# p2-001.net
KiCad netlist of a schematic drawn in EAGLE
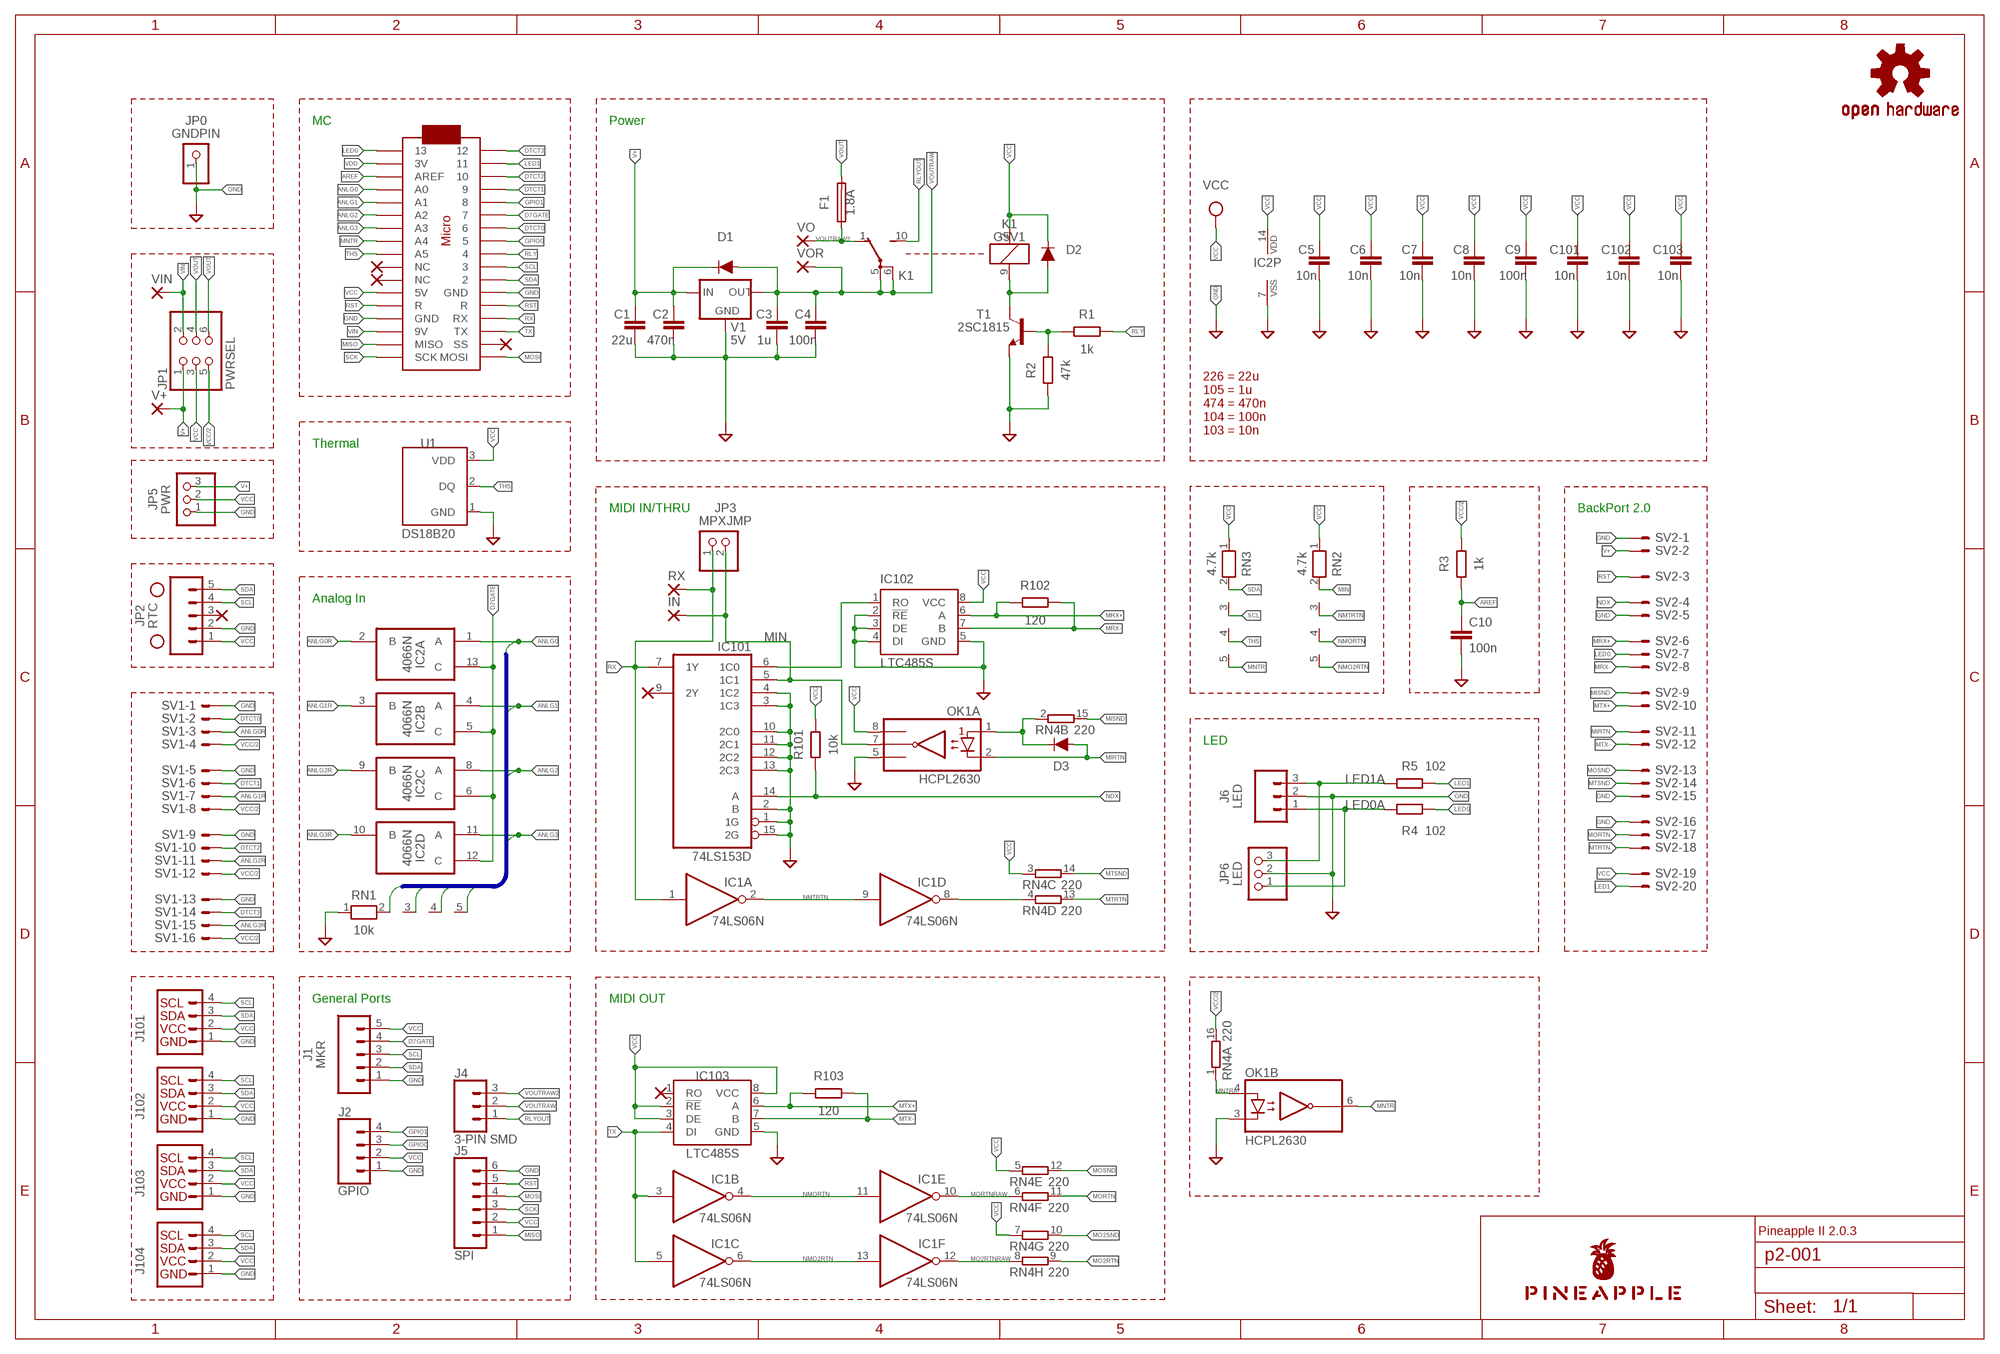
[diagram p0: schematic, sheet 1]

(export (version "E")
  (design (tool "Eeschema 10.0.6"))
  (components
    (comp (ref "C1")
      (value "22u")
      (footprint "eagle-import:C025-050X050")
      (libsource (lib "eagle-import") (part "C-EU025-050X050"))
    )
    (comp (ref "C2")
      (value "470n")
      (footprint "eagle-import:C050-024X044")
      (libsource (lib "eagle-import") (part "C-EU050-024X044"))
    )
    (comp (ref "C3")
      (value "1u")
      (footprint "eagle-import:C050-024X044")
      (libsource (lib "eagle-import") (part "C-EU050-024X044"))
    )
    (comp (ref "C4")
      (value "100n")
      (footprint "eagle-import:C025-024X044")
      (libsource (lib "eagle-import") (part "C-EU025-024X044"))
    )
    (comp (ref "C5")
      (value "10n")
      (footprint "eagle-import:C025-024X044")
      (libsource (lib "eagle-import") (part "resistor_348_C-EU025-024X044"))
    )
    (comp (ref "C6")
      (value "10n")
      (footprint "eagle-import:C025-024X044")
      (libsource (lib "eagle-import") (part "resistor_348_C-EU025-024X044"))
    )
    (comp (ref "C7")
      (value "10n")
      (footprint "eagle-import:C025-024X044")
      (libsource (lib "eagle-import") (part "resistor_348_C-EU025-024X044"))
    )
    (comp (ref "C8")
      (value "10n")
      (footprint "eagle-import:C025-024X044")
      (libsource (lib "eagle-import") (part "resistor_348_C-EU025-024X044"))
    )
    (comp (ref "C9")
      (value "100n")
      (footprint "eagle-import:C025-024X044")
      (libsource (lib "eagle-import") (part "C-EU025-024X044"))
    )
    (comp (ref "C10")
      (value "100n")
      (footprint "eagle-import:C025-024X044")
      (libsource (lib "eagle-import") (part "C-EU025-024X044"))
    )
    (comp (ref "C101")
      (value "10n")
      (footprint "eagle-import:C2012")
      (libsource (lib "eagle-import") (part "C-EUC2012"))
    )
    (comp (ref "C102")
      (value "10n")
      (footprint "eagle-import:C2012")
      (libsource (lib "eagle-import") (part "C-EUC2012"))
    )
    (comp (ref "C103")
      (value "10n")
      (footprint "eagle-import:C2012")
      (libsource (lib "eagle-import") (part "C-EUC2012"))
    )
    (comp (ref "D1")
      (value "DIODE-1N4148")
      (footprint "eagle-import:DIODE-1N4148")
      (libsource (lib "eagle-import") (part "DIODE-1N4148"))
    )
    (comp (ref "D2")
      (value "DIODE-1N4148")
      (footprint "eagle-import:DIODE-1N4148")
      (libsource (lib "eagle-import") (part "DIODE-1N4148"))
    )
    (comp (ref "D3")
      (value "DIODE-1N4148")
      (footprint "eagle-import:DIODE-1N4148")
      (libsource (lib "eagle-import") (part "DIODE-1N4148"))
    )
    (comp (ref "F1")
      (value "1.8A")
      (footprint "eagle-import:TE5")
      (libsource (lib "eagle-import") (part "TE5"))
    )
    (comp (ref "H1")
      (value "STAND-OFF")
      (footprint "eagle-import:STAND-OFF")
      (libsource (lib "eagle-import") (part "STAND-OFF"))
    )
    (comp (ref "H2")
      (value "STAND-OFF")
      (footprint "eagle-import:STAND-OFF")
      (libsource (lib "eagle-import") (part "STAND-OFF"))
    )
    (comp (ref "IC1")
      (value "74LS06N")
      (footprint "eagle-import:DIL14")
      (libsource (lib "eagle-import") (part "7406NLS"))
    )
    (comp (ref "IC2")
      (value "4066N")
      (footprint "eagle-import:DIL14")
      (libsource (lib "eagle-import") (part "4066N"))
    )
    (comp (ref "IC101")
      (value "74LS153D")
      (footprint "eagle-import:SO16")
      (libsource (lib "eagle-import") (part "74153DLS"))
    )
    (comp (ref "IC102")
      (value "LTC485S")
      (footprint "eagle-import:SOIC8")
      (libsource (lib "eagle-import") (part "LTC485S"))
    )
    (comp (ref "IC103")
      (value "LTC485S")
      (footprint "eagle-import:SOIC8")
      (libsource (lib "eagle-import") (part "LTC485S"))
    )
    (comp (ref "IN")
      (value "SMD2")
      (footprint "eagle-import:SMD1,27-2,54")
      (libsource (lib "eagle-import") (part "SMD2"))
    )
    (comp (ref "J1")
      (value "MKR")
      (footprint "eagle-import:JST-5-PTH")
      (libsource (lib "eagle-import") (part "CONN_05JST"))
    )
    (comp (ref "J2")
      (value "GPIO")
      (footprint "eagle-import:JST-4-PTH")
      (libsource (lib "eagle-import") (part "CONN_04JST-PTH"))
    )
    (comp (ref "J4")
      (value "3-PIN SMD")
      (footprint "eagle-import:JST-3-SMD")
      (libsource (lib "eagle-import") (part "SparkFun-Connectors_513_CONN_03JST-SMD"))
    )
    (comp (ref "J5")
      (value "SPI")
      (footprint "eagle-import:1X06_1.27MM")
      (libsource (lib "eagle-import") (part "CONN_061.27MM"))
    )
    (comp (ref "J6")
      (value "LED")
      (footprint "eagle-import:JST-3-PTH")
      (libsource (lib "eagle-import") (part "CONN_03JST-PTH"))
    )
    (comp (ref "J101")
      (value "Qwiic")
      (footprint "eagle-import:1X04_1MM_RA")
      (libsource (lib "eagle-import") (part "QWIIC_CONNECTORJS-1MM"))
    )
    (comp (ref "J102")
      (value "Qwiic")
      (footprint "eagle-import:1X04_1MM_RA")
      (libsource (lib "eagle-import") (part "QWIIC_CONNECTORJS-1MM"))
    )
    (comp (ref "J103")
      (value "Qwiic")
      (footprint "eagle-import:1X04_1MM_RA")
      (libsource (lib "eagle-import") (part "QWIIC_CONNECTORJS-1MM"))
    )
    (comp (ref "J104")
      (value "Qwiic")
      (footprint "eagle-import:1X04_1MM_RA")
      (libsource (lib "eagle-import") (part "QWIIC_CONNECTORJS-1MM"))
    )
    (comp (ref "JP0")
      (value "GNDPIN")
      (footprint "eagle-import:1X01")
      (libsource (lib "eagle-import") (part "PINHD-1X1"))
    )
    (comp (ref "JP1")
      (value "PWRSEL")
      (footprint "eagle-import:2X03")
      (libsource (lib "eagle-import") (part "PINHD-2X3"))
    )
    (comp (ref "JP2")
      (value "RTC")
      (footprint "eagle-import:1X05")
      (libsource (lib "eagle-import") (part "CONN_05"))
    )
    (comp (ref "JP3")
      (value "MPXJMP")
      (footprint "eagle-import:1X02")
      (libsource (lib "eagle-import") (part "PINHD-1X2"))
    )
    (comp (ref "JP5")
      (value "PWR")
      (footprint "eagle-import:1X03")
      (libsource (lib "eagle-import") (part "PINHD-1X3"))
    )
    (comp (ref "JP6")
      (value "LED")
      (footprint "eagle-import:1X03")
      (libsource (lib "eagle-import") (part "PINHD-1X3"))
    )
    (comp (ref "K1")
      (value "G5V1")
      (footprint "eagle-import:G5V1")
      (fields (field (name "MPN") "G5V-1-DC24"))
      (libsource (lib "eagle-import") (part "G5V1"))
    )
    (comp (ref "LOGO1")
      (value "OSHW-LOGOS-COPPER")
      (footprint "eagle-import:OSHW-LOGO-S_COPPER")
      (libsource (lib "eagle-import") (part "OSHW-LOGOS-COPPER"))
    )
    (comp (ref "MC1")
      (value "ARDUINOMICRO")
      (footprint "eagle-import:ARDUINOMICRO")
      (libsource (lib "eagle-import") (part "ARDUINOMICRO"))
    )
    (comp (ref "OK1")
      (value "HCPL2630")
      (footprint "eagle-import:DIL08")
      (fields (field (name "MF") "AGILENT TECHNOLOGIES") (field (name "MPN") "HCPL-2630-000E"))
      (libsource (lib "eagle-import") (part "HCPL2630"))
    )
    (comp (ref "R1")
      (value "1k")
      (footprint "eagle-import:0204_5")
      (libsource (lib "eagle-import") (part "resistor_348_R-EU_0204/5"))
    )
    (comp (ref "R2")
      (value "47k")
      (footprint "eagle-import:0204_5")
      (libsource (lib "eagle-import") (part "resistor_348_R-EU_0204/5"))
    )
    (comp (ref "R3")
      (value "1k")
      (footprint "eagle-import:0204_5")
      (libsource (lib "eagle-import") (part "resistor_348_R-EU_0204/5"))
    )
    (comp (ref "R4")
      (value "102")
      (footprint "eagle-import:0204_5")
      (libsource (lib "eagle-import") (part "resistor_348_R-EU_0204/5"))
    )
    (comp (ref "R5")
      (value "102")
      (footprint "eagle-import:0204_5")
      (libsource (lib "eagle-import") (part "resistor_348_R-EU_0204/5"))
    )
    (comp (ref "R101")
      (value "10k")
      (footprint "eagle-import:M2012")
      (libsource (lib "eagle-import") (part "R-EU_M2012"))
    )
    (comp (ref "R102")
      (value "120")
      (footprint "eagle-import:M2012")
      (libsource (lib "eagle-import") (part "R-EU_M2012"))
    )
    (comp (ref "R103")
      (value "120")
      (footprint "eagle-import:M2012")
      (libsource (lib "eagle-import") (part "R-EU_M2012"))
    )
    (comp (ref "RN1")
      (value "10k")
      (footprint "eagle-import:RN-5")
      (libsource (lib "eagle-import") (part "RN04"))
    )
    (comp (ref "RN2")
      (value "4.7k")
      (footprint "eagle-import:RN-5")
      (libsource (lib "eagle-import") (part "RN04"))
    )
    (comp (ref "RN3")
      (value "4.7k")
      (footprint "eagle-import:RN-5")
      (libsource (lib "eagle-import") (part "RN04"))
    )
    (comp (ref "RN4")
      (value "220")
      (footprint "eagle-import:DIL16")
      (libsource (lib "eagle-import") (part "8R-N"))
    )
    (comp (ref "RX")
      (value "SMD2")
      (footprint "eagle-import:SMD1,27-2,54")
      (libsource (lib "eagle-import") (part "SMD2"))
    )
    (comp (ref "SV1")
      (value "ML16LE")
      (footprint "eagle-import:ML16L")
      (libsource (lib "eagle-import") (part "ML16LE"))
    )
    (comp (ref "SV2")
      (value "ML20LE")
      (footprint "eagle-import:ML20L")
      (libsource (lib "eagle-import") (part "ML20LE"))
    )
    (comp (ref "T1")
      (value "2SC1815")
      (footprint "eagle-import:TO92-ECB")
      (libsource (lib "eagle-import") (part "2SC1815"))
    )
    (comp (ref "U$1")
      (value "PINEAPPLE450_SILK")
      (footprint "eagle-import:PINEAPPLE450_SILK")
      (libsource (lib "eagle-import") (part "PINEAPPLE450_SILK"))
    )
    (comp (ref "U1")
      (value "DS18B20")
      (footprint "eagle-import:TO-92-AMMO")
      (libsource (lib "eagle-import") (part "DS18B20"))
    )
    (comp (ref "V+")
      (value "SMD2")
      (footprint "eagle-import:SMD1,27-2,54")
      (libsource (lib "eagle-import") (part "SMD2"))
    )
    (comp (ref "V1")
      (value "5V")
      (footprint "eagle-import:78XXL")
      (libsource (lib "eagle-import") (part "78XXL"))
    )
    (comp (ref "VIN")
      (value "SMD2")
      (footprint "eagle-import:SMD1,27-2,54")
      (libsource (lib "eagle-import") (part "SMD2"))
    )
    (comp (ref "VO")
      (value "SMD2")
      (footprint "eagle-import:SMD1,27-2,54")
      (libsource (lib "eagle-import") (part "SMD2"))
    )
    (comp (ref "VOR")
      (value "SMD2")
      (footprint "eagle-import:SMD1,27-2,54")
      (libsource (lib "eagle-import") (part "SMD2"))
    )
  )
  (nets
    (net (code "1") (name "/LED0A") (class "Default")
      (node (ref "J6") (pin "1") (pinfunction "1_1") (pintype "passive"))
      (node (ref "JP6") (pin "1") (pinfunction "1_1") (pintype "passive"))
      (node (ref "R4") (pin "1") (pinfunction "1_1") (pintype "passive"))
    )
    (net (code "2") (name "/LED1A") (class "Default")
      (node (ref "J6") (pin "3") (pinfunction "3_3") (pintype "passive"))
      (node (ref "JP6") (pin "3") (pinfunction "3_3") (pintype "passive"))
      (node (ref "R5") (pin "1") (pinfunction "1_1") (pintype "passive"))
    )
    (net (code "3") (name "/MNTRA") (class "Default")
      (node (ref "OK1") (pin "4") (pinfunction "A2_4") (pintype "passive"))
      (node (ref "RN4") (pin "1") (pinfunction "1_1") (pintype "passive"))
    )
    (net (code "4") (name "/MO2RTNRAW") (class "Default")
      (node (ref "IC1") (pin "12") (pinfunction "O_12") (pintype "open_collector"))
      (node (ref "RN4") (pin "8") (pinfunction "1_8") (pintype "passive"))
    )
    (net (code "5") (name "/MORTNRAW") (class "Default")
      (node (ref "IC1") (pin "10") (pinfunction "O_10") (pintype "open_collector"))
      (node (ref "RN4") (pin "6") (pinfunction "1_6") (pintype "passive"))
    )
    (net (code "6") (name "ANLG0") (class "Default")
      (node (ref "IC2") (pin "1") (pinfunction "A_1") (pintype "tri_state"))
      (node (ref "MC1") (pin "P$31") (pinfunction "A0_P$31") (pintype "bidirectional"))
      (node (ref "RN1") (pin "2") (pinfunction "2_2") (pintype "passive"))
    )
    (net (code "7") (name "ANLG0R") (class "Default")
      (node (ref "IC2") (pin "2") (pinfunction "B_2") (pintype "tri_state"))
      (node (ref "SV1") (pin "3") (pinfunction "S_3") (pintype "passive"))
    )
    (net (code "8") (name "ANLG1") (class "Default")
      (node (ref "IC2") (pin "4") (pinfunction "A_4") (pintype "tri_state"))
      (node (ref "MC1") (pin "P$30") (pinfunction "A1_P$30") (pintype "bidirectional"))
      (node (ref "RN1") (pin "3") (pinfunction "3_3") (pintype "passive"))
    )
    (net (code "9") (name "ANLG1R") (class "Default")
      (node (ref "IC2") (pin "3") (pinfunction "B_3") (pintype "tri_state"))
      (node (ref "SV1") (pin "7") (pinfunction "S_7") (pintype "passive"))
    )
    (net (code "10") (name "ANLG2") (class "Default")
      (node (ref "IC2") (pin "8") (pinfunction "A_8") (pintype "tri_state"))
      (node (ref "MC1") (pin "P$29") (pinfunction "A2_P$29") (pintype "bidirectional"))
      (node (ref "RN1") (pin "4") (pinfunction "4_4") (pintype "passive"))
    )
    (net (code "11") (name "ANLG2R") (class "Default")
      (node (ref "IC2") (pin "9") (pinfunction "B_9") (pintype "tri_state"))
      (node (ref "SV1") (pin "11") (pinfunction "S_11") (pintype "passive"))
    )
    (net (code "12") (name "ANLG3") (class "Default")
      (node (ref "IC2") (pin "11") (pinfunction "A_11") (pintype "tri_state"))
      (node (ref "MC1") (pin "P$28") (pinfunction "A3_P$28") (pintype "bidirectional"))
      (node (ref "RN1") (pin "5") (pinfunction "5_5") (pintype "passive"))
    )
    (net (code "13") (name "ANLG3R") (class "Default")
      (node (ref "IC2") (pin "10") (pinfunction "B_10") (pintype "tri_state"))
      (node (ref "SV1") (pin "15") (pinfunction "S_15") (pintype "passive"))
    )
    (net (code "14") (name "AREF") (class "Default")
      (node (ref "C10") (pin "1") (pinfunction "1_1") (pintype "passive"))
      (node (ref "MC1") (pin "P$32") (pinfunction "AREF_P$32") (pintype "bidirectional"))
      (node (ref "R3") (pin "1") (pinfunction "1_1") (pintype "passive"))
    )
    (net (code "15") (name "D7GATE") (class "Default")
      (node (ref "IC2") (pin "12") (pinfunction "C_12") (pintype "input"))
      (node (ref "IC2") (pin "13") (pinfunction "C_13") (pintype "input"))
      (node (ref "IC2") (pin "5") (pinfunction "C_5") (pintype "input"))
      (node (ref "IC2") (pin "6") (pinfunction "C_6") (pintype "input"))
      (node (ref "J1") (pin "4") (pinfunction "4_4") (pintype "passive"))
      (node (ref "MC1") (pin "P$6") (pinfunction "7_P$6") (pintype "bidirectional"))
    )
    (net (code "16") (name "DTCT0") (class "Default")
      (node (ref "MC1") (pin "P$7") (pinfunction "6_P$7") (pintype "bidirectional"))
      (node (ref "SV1") (pin "2") (pinfunction "S_2") (pintype "passive"))
    )
    (net (code "17") (name "DTCT1") (class "Default")
      (node (ref "MC1") (pin "P$4") (pinfunction "9_P$4") (pintype "bidirectional"))
      (node (ref "SV1") (pin "6") (pinfunction "S_6") (pintype "passive"))
    )
    (net (code "18") (name "DTCT2") (class "Default")
      (node (ref "MC1") (pin "P$3") (pinfunction "10_P$3") (pintype "bidirectional"))
      (node (ref "SV1") (pin "10") (pinfunction "S_10") (pintype "passive"))
    )
    (net (code "19") (name "DTCT3") (class "Default")
      (node (ref "MC1") (pin "P$1") (pinfunction "12_P$1") (pintype "bidirectional"))
      (node (ref "SV1") (pin "14") (pinfunction "S_14") (pintype "passive"))
    )
    (net (code "20") (name "GND") (class "Default")
      (node (ref "C1") (pin "2") (pinfunction "2_2") (pintype "passive"))
      (node (ref "C10") (pin "2") (pinfunction "2_2") (pintype "passive"))
      (node (ref "C101") (pin "2") (pinfunction "2_2") (pintype "passive"))
      (node (ref "C102") (pin "2") (pinfunction "2_2") (pintype "passive"))
      (node (ref "C103") (pin "2") (pinfunction "2_2") (pintype "passive"))
      (node (ref "C2") (pin "2") (pinfunction "2_2") (pintype "passive"))
      (node (ref "C3") (pin "2") (pinfunction "2_2") (pintype "passive"))
      (node (ref "C4") (pin "2") (pinfunction "2_2") (pintype "passive"))
      (node (ref "C5") (pin "2") (pinfunction "2_2") (pintype "passive"))
      (node (ref "C6") (pin "2") (pinfunction "2_2") (pintype "passive"))
      (node (ref "C7") (pin "2") (pinfunction "2_2") (pintype "passive"))
      (node (ref "C8") (pin "2") (pinfunction "2_2") (pintype "passive"))
      (node (ref "C9") (pin "2") (pinfunction "2_2") (pintype "passive"))
      (node (ref "IC101") (pin "1") (pinfunction "1G_1") (pintype "input"))
      (node (ref "IC101") (pin "10") (pinfunction "2C0_10") (pintype "input"))
      (node (ref "IC101") (pin "11") (pinfunction "2C1_11") (pintype "input"))
      (node (ref "IC101") (pin "12") (pinfunction "2C2_12") (pintype "input"))
      (node (ref "IC101") (pin "13") (pinfunction "2C3_13") (pintype "input"))
      (node (ref "IC101") (pin "15") (pinfunction "2G_15") (pintype "input"))
      (node (ref "IC101") (pin "2") (pinfunction "B_2") (pintype "input"))
      (node (ref "IC101") (pin "3") (pinfunction "1C3_3") (pintype "input"))
      (node (ref "IC101") (pin "4") (pinfunction "1C2_4") (pintype "input"))
      (node (ref "IC102") (pin "2") (pinfunction "~{RE}_2") (pintype "input"))
      (node (ref "IC102") (pin "3") (pinfunction "DE_3") (pintype "input"))
      (node (ref "IC102") (pin "4") (pinfunction "DI_4") (pintype "input"))
      (node (ref "IC102") (pin "5") (pinfunction "GND_5") (pintype "input"))
      (node (ref "IC103") (pin "5") (pinfunction "GND_5") (pintype "input"))
      (node (ref "IC2") (pin "7") (pinfunction "VSS_7") (pintype "power_in"))
      (node (ref "J1") (pin "1") (pinfunction "1_1") (pintype "passive"))
      (node (ref "J101") (pin "1") (pinfunction "GND_1") (pintype "power_in"))
      (node (ref "J102") (pin "1") (pinfunction "GND_1") (pintype "power_in"))
      (node (ref "J103") (pin "1") (pinfunction "GND_1") (pintype "power_in"))
      (node (ref "J104") (pin "1") (pinfunction "GND_1") (pintype "power_in"))
      (node (ref "J2") (pin "1") (pinfunction "1_1") (pintype "passive"))
      (node (ref "J5") (pin "6") (pinfunction "6_6") (pintype "passive"))
      (node (ref "J6") (pin "2") (pinfunction "2_2") (pintype "passive"))
      (node (ref "JP0") (pin "1") (pinfunction "1_1") (pintype "passive"))
      (node (ref "JP2") (pin "2") (pinfunction "2_2") (pintype "passive"))
      (node (ref "JP5") (pin "1") (pinfunction "1_1") (pintype "passive"))
      (node (ref "JP6") (pin "2") (pinfunction "2_2") (pintype "passive"))
      (node (ref "MC1") (pin "P$12") (pinfunction "GND_P$12") (pintype "bidirectional"))
      (node (ref "MC1") (pin "P$21") (pinfunction "GND_P$21") (pintype "bidirectional"))
      (node (ref "OK1") (pin "3") (pinfunction "C2_3") (pintype "passive"))
      (node (ref "OK1") (pin "5") (pinfunction "GND_5") (pintype "passive"))
      (node (ref "R2") (pin "1") (pinfunction "1_1") (pintype "passive"))
      (node (ref "RN1") (pin "1") (pinfunction "1_1") (pintype "passive"))
      (node (ref "SV1") (pin "1") (pinfunction "S_1") (pintype "passive"))
      (node (ref "SV1") (pin "13") (pinfunction "S_13") (pintype "passive"))
      (node (ref "SV1") (pin "5") (pinfunction "S_5") (pintype "passive"))
      (node (ref "SV1") (pin "9") (pinfunction "S_9") (pintype "passive"))
      (node (ref "SV2") (pin "1") (pinfunction "S_1") (pintype "passive"))
      (node (ref "SV2") (pin "15") (pinfunction "S_15") (pintype "passive"))
      (node (ref "SV2") (pin "16") (pinfunction "S_16") (pintype "passive"))
      (node (ref "SV2") (pin "5") (pinfunction "S_5") (pintype "passive"))
      (node (ref "T1") (pin "E") (pinfunction "E_E") (pintype "passive"))
      (node (ref "U1") (pin "1") (pinfunction "GND_1") (pintype "power_in"))
      (node (ref "V1") (pin "GND") (pinfunction "GND_GND") (pintype "input"))
    )
    (net (code "21") (name "GPIO0") (class "Default")
      (node (ref "J2") (pin "3") (pinfunction "3_3") (pintype "passive"))
      (node (ref "MC1") (pin "P$8") (pinfunction "5_P$8") (pintype "bidirectional"))
    )
    (net (code "22") (name "GPIO1") (class "Default")
      (node (ref "J2") (pin "4") (pinfunction "4_4") (pintype "passive"))
      (node (ref "MC1") (pin "P$5") (pinfunction "8_P$5") (pintype "bidirectional"))
    )
    (net (code "23") (name "LED0") (class "Default")
      (node (ref "MC1") (pin "P$34") (pinfunction "13_P$34") (pintype "bidirectional"))
      (node (ref "R4") (pin "2") (pinfunction "2_2") (pintype "passive"))
      (node (ref "SV2") (pin "7") (pinfunction "S_7") (pintype "passive"))
    )
    (net (code "24") (name "LED1") (class "Default")
      (node (ref "MC1") (pin "P$2") (pinfunction "11_P$2") (pintype "bidirectional"))
      (node (ref "R5") (pin "2") (pinfunction "2_2") (pintype "passive"))
      (node (ref "SV2") (pin "20") (pinfunction "S_20") (pintype "passive"))
    )
    (net (code "25") (name "MIN") (class "Default")
      (node (ref "IC101") (pin "5") (pinfunction "1C1_5") (pintype "input"))
      (node (ref "IN") (pin "1") (pinfunction "P_1") (pintype "passive"))
      (node (ref "JP3") (pin "2") (pinfunction "2_2") (pintype "passive"))
      (node (ref "OK1") (pin "7") (pinfunction "VO1_7") (pintype "passive"))
      (node (ref "RN2") (pin "2") (pinfunction "2_2") (pintype "passive"))
    )
    (net (code "26") (name "MIRTN") (class "Default")
      (node (ref "D3") (pin "A") (pinfunction "A_A") (pintype "passive"))
      (node (ref "OK1") (pin "2") (pinfunction "C1_2") (pintype "passive"))
      (node (ref "SV2") (pin "11") (pinfunction "S_11") (pintype "passive"))
    )
    (net (code "27") (name "MISND") (class "Default")
      (node (ref "RN4") (pin "15") (pinfunction "2_15") (pintype "passive"))
      (node (ref "SV2") (pin "9") (pinfunction "S_9") (pintype "passive"))
    )
    (net (code "28") (name "MISO") (class "Default")
      (node (ref "J5") (pin "1") (pinfunction "1_1") (pintype "passive"))
      (node (ref "MC1") (pin "P$19") (pinfunction "MISO_P$19") (pintype "bidirectional"))
    )
    (net (code "29") (name "MNTR") (class "Default")
      (node (ref "MC1") (pin "P$27") (pinfunction "A4_P$27") (pintype "bidirectional"))
      (node (ref "OK1") (pin "6") (pinfunction "VO2_6") (pintype "passive"))
      (node (ref "RN3") (pin "5") (pinfunction "5_5") (pintype "passive"))
    )
    (net (code "30") (name "MO2RTN") (class "Default")
      (node (ref "RN4") (pin "9") (pinfunction "2_9") (pintype "passive"))
    )
    (net (code "31") (name "MO2SND") (class "Default")
      (node (ref "RN4") (pin "10") (pinfunction "2_10") (pintype "passive"))
    )
    (net (code "32") (name "MORTN") (class "Default")
      (node (ref "RN4") (pin "11") (pinfunction "2_11") (pintype "passive"))
      (node (ref "SV2") (pin "17") (pinfunction "S_17") (pintype "passive"))
    )
    (net (code "33") (name "MOSI") (class "Default")
      (node (ref "J5") (pin "4") (pinfunction "4_4") (pintype "passive"))
      (node (ref "MC1") (pin "P$17") (pinfunction "MOSI_P$17") (pintype "bidirectional"))
    )
    (net (code "34") (name "MOSND") (class "Default")
      (node (ref "RN4") (pin "12") (pinfunction "2_12") (pintype "passive"))
      (node (ref "SV2") (pin "13") (pinfunction "S_13") (pintype "passive"))
    )
    (net (code "35") (name "MRX+") (class "Default")
      (node (ref "IC102") (pin "6") (pinfunction "A_6") (pintype "bidirectional"))
      (node (ref "R102") (pin "1") (pinfunction "1_1") (pintype "passive"))
      (node (ref "SV2") (pin "6") (pinfunction "S_6") (pintype "passive"))
    )
    (net (code "36") (name "MRX-") (class "Default")
      (node (ref "IC102") (pin "7") (pinfunction "B_7") (pintype "bidirectional"))
      (node (ref "R102") (pin "2") (pinfunction "2_2") (pintype "passive"))
      (node (ref "SV2") (pin "8") (pinfunction "S_8") (pintype "passive"))
    )
    (net (code "37") (name "MTRTN") (class "Default")
      (node (ref "RN4") (pin "13") (pinfunction "2_13") (pintype "passive"))
      (node (ref "SV2") (pin "18") (pinfunction "S_18") (pintype "passive"))
    )
    (net (code "38") (name "MTSND") (class "Default")
      (node (ref "RN4") (pin "14") (pinfunction "2_14") (pintype "passive"))
      (node (ref "SV2") (pin "14") (pinfunction "S_14") (pintype "passive"))
    )
    (net (code "39") (name "MTX+") (class "Default")
      (node (ref "IC103") (pin "6") (pinfunction "A_6") (pintype "bidirectional"))
      (node (ref "R103") (pin "1") (pinfunction "1_1") (pintype "passive"))
      (node (ref "SV2") (pin "10") (pinfunction "S_10") (pintype "passive"))
    )
    (net (code "40") (name "MTX-") (class "Default")
      (node (ref "IC103") (pin "7") (pinfunction "B_7") (pintype "bidirectional"))
      (node (ref "R103") (pin "2") (pinfunction "2_2") (pintype "passive"))
      (node (ref "SV2") (pin "12") (pinfunction "S_12") (pintype "passive"))
    )
    (net (code "41") (name "NDX") (class "Default")
      (node (ref "IC101") (pin "14") (pinfunction "A_14") (pintype "input"))
      (node (ref "R101") (pin "1") (pinfunction "1_1") (pintype "passive"))
      (node (ref "SV2") (pin "4") (pinfunction "S_4") (pintype "passive"))
    )
    (net (code "42") (name "NMO2RTN") (class "Default")
      (node (ref "IC1") (pin "13") (pinfunction "I_13") (pintype "input"))
      (node (ref "IC1") (pin "6") (pinfunction "O_6") (pintype "open_collector"))
      (node (ref "RN2") (pin "5") (pinfunction "5_5") (pintype "passive"))
    )
    (net (code "43") (name "NMORTN") (class "Default")
      (node (ref "IC1") (pin "11") (pinfunction "I_11") (pintype "input"))
      (node (ref "IC1") (pin "4") (pinfunction "O_4") (pintype "open_collector"))
      (node (ref "RN2") (pin "4") (pinfunction "4_4") (pintype "passive"))
    )
    (net (code "44") (name "NMTRTN") (class "Default")
      (node (ref "IC1") (pin "2") (pinfunction "O_2") (pintype "open_collector"))
      (node (ref "IC1") (pin "9") (pinfunction "I_9") (pintype "input"))
      (node (ref "RN2") (pin "3") (pinfunction "3_3") (pintype "passive"))
    )
    (net (code "45") (name "Net-(IC1D-O)") (class "Default")
      (node (ref "IC1") (pin "8") (pinfunction "O_8") (pintype "open_collector"))
      (node (ref "RN4") (pin "4") (pinfunction "1_4") (pintype "passive"))
    )
    (net (code "46") (name "Net-(IC101A-1C0)") (class "Default")
      (node (ref "IC101") (pin "6") (pinfunction "1C0_6") (pintype "input"))
      (node (ref "IC102") (pin "1") (pinfunction "RO_1") (pintype "output"))
    )
    (net (code "47") (name "Net-(K1A-2)") (class "Default")
      (node (ref "D2") (pin "A") (pinfunction "A_A") (pintype "passive"))
      (node (ref "K1") (pin "9") (pinfunction "2_9") (pintype "passive"))
      (node (ref "T1") (pin "C") (pinfunction "C_C") (pintype "passive"))
    )
    (net (code "48") (name "Net-(OK1A-A1)") (class "Default")
      (node (ref "D3") (pin "C") (pinfunction "C_C") (pintype "passive"))
      (node (ref "OK1") (pin "1") (pinfunction "A1_1") (pintype "passive"))
      (node (ref "RN4") (pin "2") (pinfunction "1_2") (pintype "passive"))
    )
    (net (code "49") (name "Net-(R1-Pad1)") (class "Default")
      (node (ref "R1") (pin "1") (pinfunction "1_1") (pintype "passive"))
      (node (ref "R2") (pin "2") (pinfunction "2_2") (pintype "passive"))
      (node (ref "T1") (pin "B") (pinfunction "B_B") (pintype "passive"))
    )
    (net (code "50") (name "RLY") (class "Default")
      (node (ref "MC1") (pin "P$9") (pinfunction "4_P$9") (pintype "bidirectional"))
      (node (ref "R1") (pin "2") (pinfunction "2_2") (pintype "passive"))
    )
    (net (code "51") (name "RLYOUT") (class "Default")
      (node (ref "J4") (pin "1") (pinfunction "1_1") (pintype "passive"))
      (node (ref "K1") (pin "10") (pinfunction "S_10") (pintype "passive"))
    )
    (net (code "52") (name "RST") (class "Default")
      (node (ref "J5") (pin "5") (pinfunction "5_5") (pintype "passive"))
      (node (ref "MC1") (pin "P$13") (pinfunction "R_P$13") (pintype "bidirectional"))
      (node (ref "MC1") (pin "P$22") (pinfunction "R_P$22") (pintype "bidirectional"))
      (node (ref "SV2") (pin "3") (pinfunction "S_3") (pintype "passive"))
    )
    (net (code "53") (name "RX") (class "Default")
      (node (ref "IC1") (pin "1") (pinfunction "I_1") (pintype "input"))
      (node (ref "IC101") (pin "7") (pinfunction "1Y_7") (pintype "output"))
      (node (ref "JP3") (pin "1") (pinfunction "1_1") (pintype "passive"))
      (node (ref "MC1") (pin "P$14") (pinfunction "RX_P$14") (pintype "bidirectional"))
      (node (ref "RX") (pin "1") (pinfunction "P_1") (pintype "passive"))
    )
    (net (code "54") (name "SCK") (class "Default")
      (node (ref "J5") (pin "3") (pinfunction "3_3") (pintype "passive"))
      (node (ref "MC1") (pin "P$18") (pinfunction "SCK_P$18") (pintype "bidirectional"))
    )
    (net (code "55") (name "SCL") (class "Default")
      (node (ref "J1") (pin "3") (pinfunction "3_3") (pintype "passive"))
      (node (ref "J101") (pin "4") (pinfunction "SCL_4") (pintype "passive"))
      (node (ref "J102") (pin "4") (pinfunction "SCL_4") (pintype "passive"))
      (node (ref "J103") (pin "4") (pinfunction "SCL_4") (pintype "passive"))
      (node (ref "J104") (pin "4") (pinfunction "SCL_4") (pintype "passive"))
      (node (ref "JP2") (pin "4") (pinfunction "4_4") (pintype "passive"))
      (node (ref "MC1") (pin "P$10") (pinfunction "3_P$10") (pintype "bidirectional"))
      (node (ref "RN3") (pin "3") (pinfunction "3_3") (pintype "passive"))
    )
    (net (code "56") (name "SDA") (class "Default")
      (node (ref "J1") (pin "2") (pinfunction "2_2") (pintype "passive"))
      (node (ref "J101") (pin "3") (pinfunction "SDA_3") (pintype "passive"))
      (node (ref "J102") (pin "3") (pinfunction "SDA_3") (pintype "passive"))
      (node (ref "J103") (pin "3") (pinfunction "SDA_3") (pintype "passive"))
      (node (ref "J104") (pin "3") (pinfunction "SDA_3") (pintype "passive"))
      (node (ref "JP2") (pin "5") (pinfunction "5_5") (pintype "passive"))
      (node (ref "MC1") (pin "P$11") (pinfunction "2_P$11") (pintype "bidirectional"))
      (node (ref "RN3") (pin "2") (pinfunction "2_2") (pintype "passive"))
    )
    (net (code "57") (name "THS") (class "Default")
      (node (ref "MC1") (pin "P$26") (pinfunction "A5_P$26") (pintype "bidirectional"))
      (node (ref "RN3") (pin "4") (pinfunction "4_4") (pintype "passive"))
      (node (ref "U1") (pin "2") (pinfunction "DQ_2") (pintype "bidirectional"))
    )
    (net (code "58") (name "TX") (class "Default")
      (node (ref "IC1") (pin "3") (pinfunction "I_3") (pintype "input"))
      (node (ref "IC1") (pin "5") (pinfunction "I_5") (pintype "input"))
      (node (ref "IC103") (pin "4") (pinfunction "DI_4") (pintype "input"))
      (node (ref "MC1") (pin "P$15") (pinfunction "TX_P$15") (pintype "bidirectional"))
    )
    (net (code "59") (name "V+") (class "Default")
      (node (ref "C1") (pin "1") (pinfunction "1_1") (pintype "passive"))
      (node (ref "C2") (pin "1") (pinfunction "1_1") (pintype "passive"))
      (node (ref "D1") (pin "C") (pinfunction "C_C") (pintype "passive"))
      (node (ref "JP1") (pin "1") (pinfunction "1_1") (pintype "passive"))
      (node (ref "JP5") (pin "3") (pinfunction "3_3") (pintype "passive"))
      (node (ref "SV2") (pin "2") (pinfunction "S_2") (pintype "passive"))
      (node (ref "V+") (pin "1") (pinfunction "P_1") (pintype "passive"))
      (node (ref "V1") (pin "IN") (pinfunction "IN_IN") (pintype "input"))
    )
    (net (code "60") (name "VCC") (class "Default")
      (node (ref "C101") (pin "1") (pinfunction "1_1") (pintype "passive"))
      (node (ref "C102") (pin "1") (pinfunction "1_1") (pintype "passive"))
      (node (ref "C103") (pin "1") (pinfunction "1_1") (pintype "passive"))
      (node (ref "C5") (pin "1") (pinfunction "1_1") (pintype "passive"))
      (node (ref "C6") (pin "1") (pinfunction "1_1") (pintype "passive"))
      (node (ref "C7") (pin "1") (pinfunction "1_1") (pintype "passive"))
      (node (ref "C8") (pin "1") (pinfunction "1_1") (pintype "passive"))
      (node (ref "C9") (pin "1") (pinfunction "1_1") (pintype "passive"))
      (node (ref "D2") (pin "C") (pinfunction "C_C") (pintype "passive"))
      (node (ref "IC102") (pin "8") (pinfunction "VCC_8") (pintype "input"))
      (node (ref "IC103") (pin "2") (pinfunction "~{RE}_2") (pintype "input"))
      (node (ref "IC103") (pin "3") (pinfunction "DE_3") (pintype "input"))
      (node (ref "IC103") (pin "8") (pinfunction "VCC_8") (pintype "input"))
      (node (ref "IC2") (pin "14") (pinfunction "VDD_14") (pintype "power_in"))
      (node (ref "J1") (pin "5") (pinfunction "5_5") (pintype "passive"))
      (node (ref "J101") (pin "2") (pinfunction "VCC_2") (pintype "power_in"))
      (node (ref "J102") (pin "2") (pinfunction "VCC_2") (pintype "power_in"))
      (node (ref "J103") (pin "2") (pinfunction "VCC_2") (pintype "power_in"))
      (node (ref "J104") (pin "2") (pinfunction "VCC_2") (pintype "power_in"))
      (node (ref "J2") (pin "2") (pinfunction "2_2") (pintype "passive"))
      (node (ref "J5") (pin "2") (pinfunction "2_2") (pintype "passive"))
      (node (ref "JP1") (pin "3") (pinfunction "3_3") (pintype "passive"))
      (node (ref "JP2") (pin "1") (pinfunction "1_1") (pintype "passive"))
      (node (ref "JP5") (pin "2") (pinfunction "2_2") (pintype "passive"))
      (node (ref "K1") (pin "2") (pinfunction "1_2") (pintype "passive"))
      (node (ref "MC1") (pin "P$23") (pinfunction "5V_P$23") (pintype "bidirectional"))
      (node (ref "OK1") (pin "8") (pinfunction "VCC_8") (pintype "passive"))
      (node (ref "R101") (pin "2") (pinfunction "2_2") (pintype "passive"))
      (node (ref "RN2") (pin "1") (pinfunction "1_1") (pintype "passive"))
      (node (ref "RN3") (pin "1") (pinfunction "1_1") (pintype "passive"))
      (node (ref "RN4") (pin "3") (pinfunction "1_3") (pintype "passive"))
      (node (ref "RN4") (pin "5") (pinfunction "1_5") (pintype "passive"))
      (node (ref "RN4") (pin "7") (pinfunction "1_7") (pintype "passive"))
      (node (ref "SV2") (pin "19") (pinfunction "S_19") (pintype "passive"))
      (node (ref "U1") (pin "3") (pinfunction "VDD_3") (pintype "power_in"))
    )
    (net (code "61") (name "VCC{slash}2") (class "Default")
      (node (ref "JP1") (pin "5") (pinfunction "5_5") (pintype "passive"))
      (node (ref "R3") (pin "2") (pinfunction "2_2") (pintype "passive"))
      (node (ref "RN4") (pin "16") (pinfunction "2_16") (pintype "passive"))
      (node (ref "SV1") (pin "12") (pinfunction "S_12") (pintype "passive"))
      (node (ref "SV1") (pin "16") (pinfunction "S_16") (pintype "passive"))
      (node (ref "SV1") (pin "4") (pinfunction "S_4") (pintype "passive"))
      (node (ref "SV1") (pin "8") (pinfunction "S_8") (pintype "passive"))
    )
    (net (code "62") (name "VDD") (class "Default")
      (node (ref "MC1") (pin "P$33") (pinfunction "3V_P$33") (pintype "bidirectional"))
    )
    (net (code "63") (name "VIN") (class "Default")
      (node (ref "JP1") (pin "2") (pinfunction "2_2") (pintype "passive"))
      (node (ref "MC1") (pin "P$20") (pinfunction "9V_P$20") (pintype "bidirectional"))
      (node (ref "VIN") (pin "1") (pinfunction "P_1") (pintype "passive"))
    )
    (net (code "64") (name "VOUT") (class "Default")
      (node (ref "F1") (pin "2") (pinfunction "2_2") (pintype "passive"))
      (node (ref "JP1") (pin "4") (pinfunction "4_4") (pintype "passive"))
      (node (ref "JP1") (pin "6") (pinfunction "6_6") (pintype "passive"))
    )
    (net (code "65") (name "VOUTRAW") (class "Default")
      (node (ref "C3") (pin "1") (pinfunction "1_1") (pintype "passive"))
      (node (ref "C4") (pin "1") (pinfunction "1_1") (pintype "passive"))
      (node (ref "D1") (pin "A") (pinfunction "A_A") (pintype "passive"))
      (node (ref "J4") (pin "2") (pinfunction "2_2") (pintype "passive"))
      (node (ref "K1") (pin "5") (pinfunction "P_5") (pintype "passive"))
      (node (ref "K1") (pin "6") (pinfunction "P_6") (pintype "passive"))
      (node (ref "V1") (pin "OUT") (pinfunction "OUT_OUT") (pintype "passive"))
      (node (ref "VOR") (pin "1") (pinfunction "P_1") (pintype "passive"))
    )
    (net (code "66") (name "VOUTRAW2") (class "Default")
      (node (ref "F1") (pin "1") (pinfunction "1_1") (pintype "passive"))
      (node (ref "J4") (pin "3") (pinfunction "3_3") (pintype "passive"))
      (node (ref "K1") (pin "1") (pinfunction "O_1") (pintype "passive"))
      (node (ref "VO") (pin "1") (pinfunction "P_1") (pintype "passive"))
    )
    (net (code "67") (name "unconnected-(IC101A-2Y-Pad9)") (class "Default")
      (node (ref "IC101") (pin "9") (pinfunction "2Y_9") (pintype "output"))
    )
    (net (code "68") (name "unconnected-(IC103-RO-Pad1)") (class "Default")
      (node (ref "IC103") (pin "1") (pinfunction "RO_1") (pintype "output"))
    )
    (net (code "69") (name "unconnected-(JP2-Pad3)") (class "Default")
      (node (ref "JP2") (pin "3") (pinfunction "3_3") (pintype "passive"))
    )
    (net (code "70") (name "unconnected-(MC1-NC-PadP$24)") (class "Default")
      (node (ref "MC1") (pin "P$24") (pinfunction "NC_P$24") (pintype "bidirectional"))
    )
    (net (code "71") (name "unconnected-(MC1-NC-PadP$25)") (class "Default")
      (node (ref "MC1") (pin "P$25") (pinfunction "NC_P$25") (pintype "bidirectional"))
    )
    (net (code "72") (name "unconnected-(MC1-SS-PadP$16)") (class "Default")
      (node (ref "MC1") (pin "P$16") (pinfunction "SS_P$16") (pintype "bidirectional"))
    )
  )
)
